# esp8266_schematic.net
KiCad netlist of a schematic drawn in EAGLE
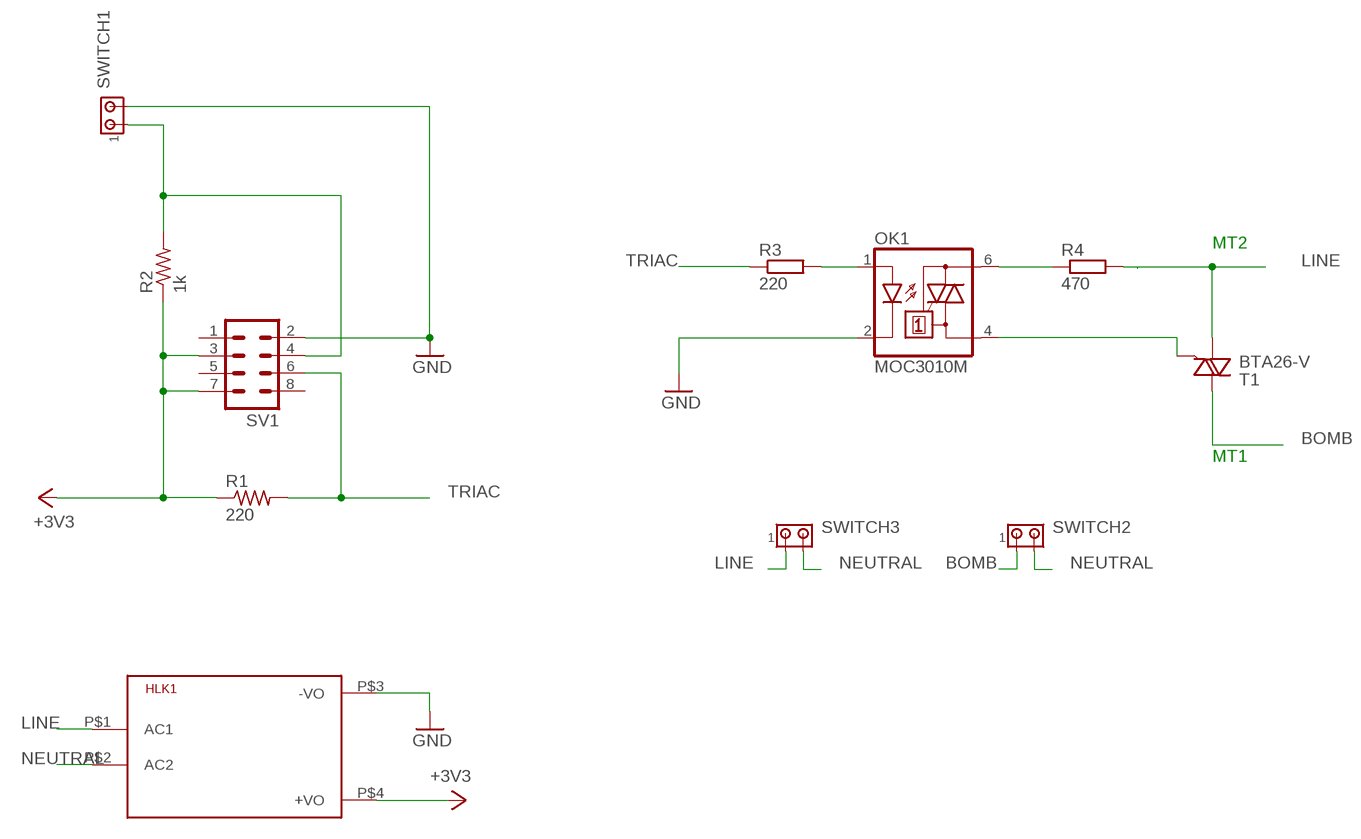
[diagram p0: schematic, sheet 1]

(export (version "E")
  (design (tool "Eeschema 10.0.6"))
  (components
    (comp (ref "HLK1")
      (value "HLK-PM013W")
      (footprint "eagle-import:HLK-PM01")
      (libsource (lib "eagle-import") (part "HLK-PM013W"))
    )
    (comp (ref "OK1")
      (value "MOC3010M")
      (footprint "eagle-import:DIL06")
      (fields (field (name "MF") "FAIRCHILD SEMICONDUCTOR") (field (name "MPN") "MOC3010-M"))
      (libsource (lib "eagle-import") (part "MOC30M10"))
    )
    (comp (ref "R1")
      (value "220")
      (footprint "eagle-import:0207_2V")
      (libsource (lib "eagle-import") (part "R-US_0207/2V"))
    )
    (comp (ref "R2")
      (value "1k")
      (footprint "eagle-import:0207_2V")
      (libsource (lib "eagle-import") (part "R-US_0207/2V"))
    )
    (comp (ref "R3")
      (value "220")
      (footprint "eagle-import:0204_5")
      (libsource (lib "eagle-import") (part "R-EU_0204/5"))
    )
    (comp (ref "R4")
      (value "470")
      (footprint "eagle-import:0207_15")
      (libsource (lib "eagle-import") (part "R-EU_0207/15"))
    )
    (comp (ref "SV1")
      (value "MA04-2")
      (footprint "eagle-import:MA04-2")
      (libsource (lib "eagle-import") (part "MA04-2"))
    )
    (comp (ref "SWITCH1")
      (value "MTA02-100")
      (footprint "eagle-import:10X02MTA")
      (libsource (lib "eagle-import") (part "MTA02-100"))
    )
    (comp (ref "SWITCH2")
      (value "MTA02-100")
      (footprint "eagle-import:10X02MTA")
      (libsource (lib "eagle-import") (part "MTA02-100"))
    )
    (comp (ref "SWITCH3")
      (value "MTA02-100")
      (footprint "eagle-import:10X02MTA")
      (libsource (lib "eagle-import") (part "MTA02-100"))
    )
    (comp (ref "T1")
      (value "BTA26-V")
      (footprint "eagle-import:TOP3S-1")
      (libsource (lib "eagle-import") (part "BTA26-V"))
    )
  )
  (nets
    (net (code "1") (name "+3V3") (class "Default")
      (node (ref "HLK1") (pin "P$4") (pinfunction "+VO_P$4") (pintype "bidirectional"))
      (node (ref "R1") (pin "1") (pinfunction "1_1") (pintype "passive"))
      (node (ref "R2") (pin "1") (pinfunction "1_1") (pintype "passive"))
      (node (ref "SV1") (pin "3") (pinfunction "3_3") (pintype "passive"))
      (node (ref "SV1") (pin "7") (pinfunction "7_7") (pintype "passive"))
    )
    (net (code "2") (name "/BOMB") (class "Default")
      (node (ref "SWITCH2") (pin "1") (pinfunction "1_1") (pintype "passive"))
      (node (ref "T1") (pin "A2") (pinfunction "A2_A2") (pintype "passive"))
    )
    (net (code "3") (name "/LINE") (class "Default")
      (node (ref "HLK1") (pin "P$1") (pinfunction "AC1_P$1") (pintype "bidirectional"))
      (node (ref "R4") (pin "2") (pinfunction "2_2") (pintype "passive"))
      (node (ref "SWITCH3") (pin "1") (pinfunction "1_1") (pintype "passive"))
      (node (ref "T1") (pin "A1") (pinfunction "A1_A1") (pintype "passive"))
    )
    (net (code "4") (name "/NEUTRAL") (class "Default")
      (node (ref "HLK1") (pin "P$2") (pinfunction "AC2_P$2") (pintype "bidirectional"))
      (node (ref "SWITCH2") (pin "2") (pinfunction "2_2") (pintype "passive"))
      (node (ref "SWITCH3") (pin "2") (pinfunction "2_2") (pintype "passive"))
    )
    (net (code "5") (name "/TRIAC") (class "Default")
      (node (ref "R1") (pin "2") (pinfunction "2_2") (pintype "passive"))
      (node (ref "R3") (pin "1") (pinfunction "1_1") (pintype "passive"))
      (node (ref "SV1") (pin "6") (pinfunction "6_6") (pintype "passive"))
    )
    (net (code "6") (name "GND") (class "Default")
      (node (ref "HLK1") (pin "P$3") (pinfunction "-VO_P$3") (pintype "bidirectional"))
      (node (ref "OK1") (pin "2") (pinfunction "C_2") (pintype "passive"))
      (node (ref "SV1") (pin "2") (pinfunction "2_2") (pintype "passive"))
      (node (ref "SWITCH1") (pin "2") (pinfunction "2_2") (pintype "passive"))
    )
    (net (code "7") (name "Net-(OK1-A)") (class "Default")
      (node (ref "OK1") (pin "1") (pinfunction "A_1") (pintype "passive"))
      (node (ref "R3") (pin "2") (pinfunction "2_2") (pintype "passive"))
    )
    (net (code "8") (name "Net-(OK1-A1)") (class "Default")
      (node (ref "OK1") (pin "4") (pinfunction "A1_4") (pintype "passive"))
      (node (ref "T1") (pin "G") (pinfunction "G_G") (pintype "passive"))
    )
    (net (code "9") (name "Net-(OK1-A2)") (class "Default")
      (node (ref "OK1") (pin "6") (pinfunction "A2_6") (pintype "passive"))
      (node (ref "R4") (pin "1") (pinfunction "1_1") (pintype "passive"))
    )
    (net (code "10") (name "Net-(R2-Pad2)") (class "Default")
      (node (ref "R2") (pin "2") (pinfunction "2_2") (pintype "passive"))
      (node (ref "SV1") (pin "4") (pinfunction "4_4") (pintype "passive"))
      (node (ref "SWITCH1") (pin "1") (pinfunction "1_1") (pintype "passive"))
    )
    (net (code "11") (name "unconnected-(SV1-Pad1)") (class "Default")
      (node (ref "SV1") (pin "1") (pinfunction "1_1") (pintype "passive"))
    )
    (net (code "12") (name "unconnected-(SV1-Pad5)") (class "Default")
      (node (ref "SV1") (pin "5") (pinfunction "5_5") (pintype "passive"))
    )
    (net (code "13") (name "unconnected-(SV1-Pad8)") (class "Default")
      (node (ref "SV1") (pin "8") (pinfunction "8_8") (pintype "passive"))
    )
  )
)
